# SHDN-IMD-S05-V00-IsolatedCAN.net
KiCad netlist of a schematic drawn in Altium Designer
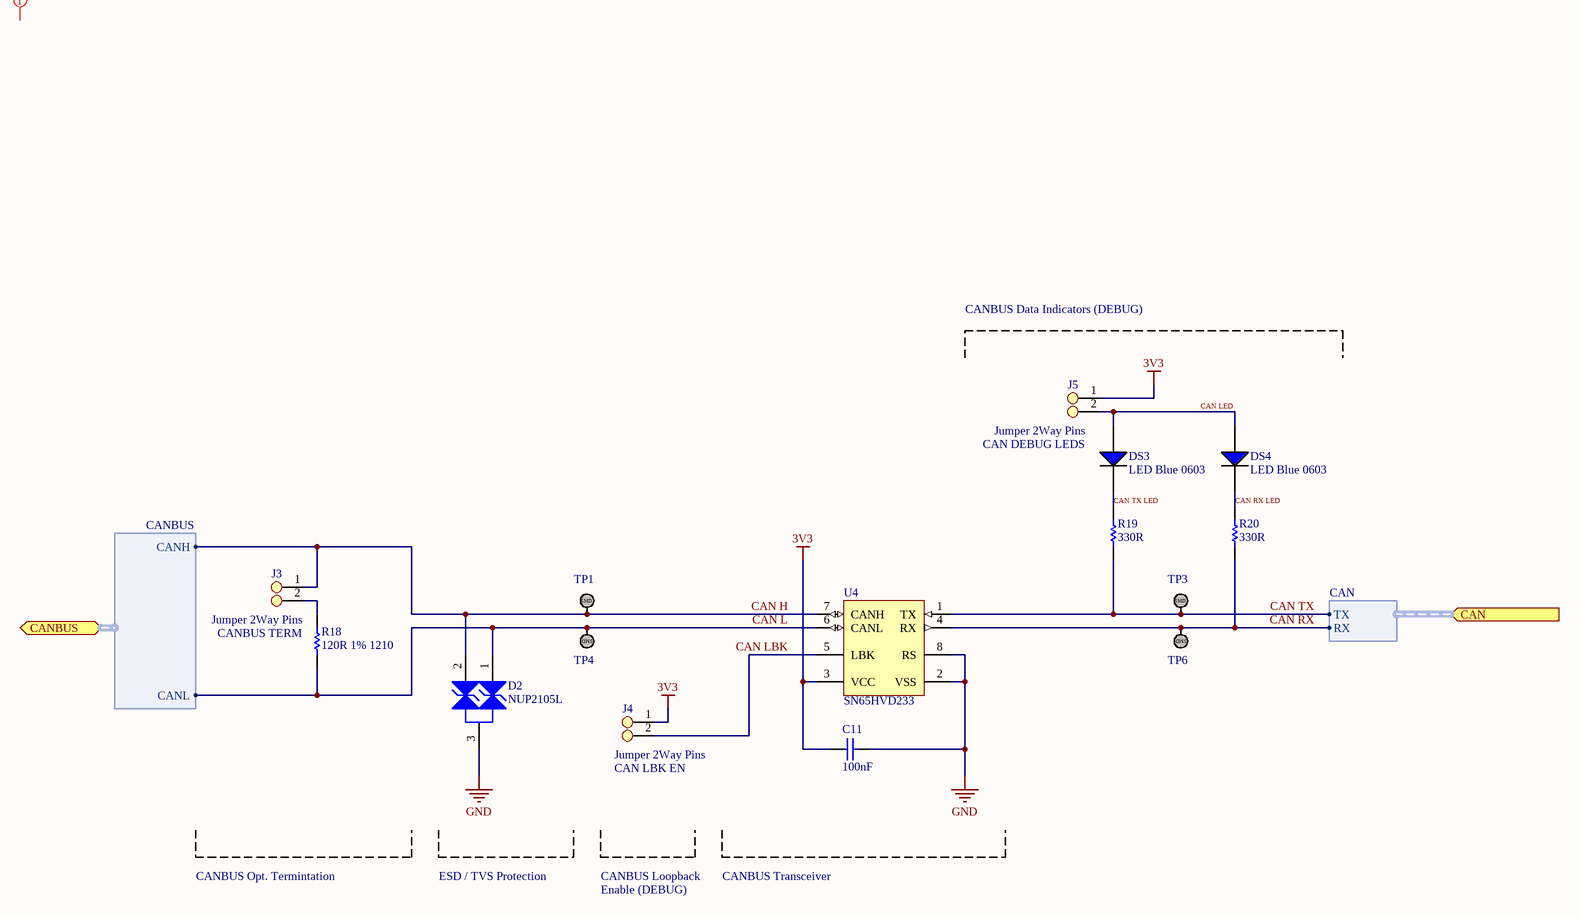
[diagram p0: SHDN-IMD-S05-V00-IsolatedCAN.SchDoc]

(export (version "E")
  (design (tool "Eeschema 10.0.6"))
  (components
    (comp (ref "C11")
      (value "100nF")
      (footprint "Cap_Ceramic_0603")
      (description "Capacitor, Ceramic, SMD, 100nF, 100V, 5%, X7R, 0603")
      (libsource (lib "StandardCapacitors") (part "100nF 100V 5% X7R 0603"))
    )
    (comp (ref "D2")
      (value "NUP2105L")
      (footprint "NUP2105L")
      (libsource (lib "QUTMS_CANLibrary") (part "NUP2105L"))
    )
    (comp (ref "DS3")
      (value "LED Blue 0603")
      (footprint "LED BLUE 0603")
      (libsource (lib "QUTMS_LEDLibrary") (part "LED BLUE 0603"))
    )
    (comp (ref "DS4")
      (value "LED Blue 0603")
      (footprint "LED BLUE 0603")
      (libsource (lib "QUTMS_LEDLibrary") (part "LED BLUE 0603"))
    )
    (comp (ref "J3")
      (value "Jumper 2Way Pins")
      (footprint "Jumper_2Way_Pin")
      (description "Jumper 2Way Side Pins")
      (libsource (lib "QUTMS_JumperLibrary") (part "Jumper 2Way Side Pins"))
    )
    (comp (ref "J4")
      (value "Jumper 2Way Pins")
      (footprint "Jumper_2Way_Pin")
      (description "Jumper 2Way Side Pins")
      (libsource (lib "QUTMS_JumperLibrary") (part "Jumper 2Way Side Pins"))
    )
    (comp (ref "J5")
      (value "Jumper 2Way Pins")
      (footprint "Jumper_2Way_Pin")
      (description "Jumper 2Way Side Pins")
      (libsource (lib "QUTMS_JumperLibrary") (part "Jumper 2Way Side Pins"))
    )
    (comp (ref "R18")
      (value "120R 1% 1210")
      (footprint "Res_ThinFilm_1210")
      (description "Resistor, SMD, 120R, 0.25W, 1%, 1210")
      (libsource (lib "StandardResistors") (part "120R 1% 1210"))
    )
    (comp (ref "R19")
      (value "330R")
      (footprint "Res_ThinFilm_0603")
      (description "Resistor, SMD, 330R, 0.1W, 5%, 0603")
      (libsource (lib "StandardResistors") (part "330R 5% 0603"))
    )
    (comp (ref "R20")
      (value "330R")
      (footprint "Res_ThinFilm_0603")
      (description "Resistor, SMD, 330R, 0.1W, 5%, 0603")
      (libsource (lib "StandardResistors") (part "330R 5% 0603"))
    )
    (comp (ref "TP1")
      (value "TestPoint_SMD")
      (footprint "TestPointSMD")
      (libsource (lib "StandardTest") (part "TestPoint_SMD"))
    )
    (comp (ref "TP3")
      (value "TestPoint_SMD")
      (footprint "TestPointSMD")
      (libsource (lib "StandardTest") (part "TestPoint_SMD"))
    )
    (comp (ref "TP4")
      (value "TestPoint_SMD")
      (footprint "TestPointSMD")
      (libsource (lib "StandardTest") (part "TestPoint_SMD"))
    )
    (comp (ref "TP6")
      (value "TestPoint_SMD")
      (footprint "TestPointSMD")
      (libsource (lib "StandardTest") (part "TestPoint_SMD"))
    )
    (comp (ref "U4")
      (value "SN65HVD233")
      (footprint "SN65HVD233DR")
      (libsource (lib "QUTMS_CANLibrary") (part "SN65HVD233"))
    )
  )
  (nets
    (net (code "3") (name "/CAN H") (class "Default")
      (node (ref "D2") (pin "2") (pinfunction "2_2") (pintype "passive"))
      (node (ref "J3") (pin "1") (pinfunction "1_1") (pintype "passive"))
      (node (ref "TP1") (pin "1") (pinfunction "1_1") (pintype "passive"))
      (node (ref "U4") (pin "7") (pinfunction "CANH_7") (pintype "bidirectional"))
    )
    (net (code "4") (name "/CAN L") (class "Default")
      (node (ref "D2") (pin "1") (pinfunction "1_1") (pintype "passive"))
      (node (ref "R18") (pin "1") (pinfunction "1_1") (pintype "passive"))
      (node (ref "TP4") (pin "1") (pinfunction "1_1") (pintype "passive"))
      (node (ref "U4") (pin "6") (pinfunction "CANL_6") (pintype "bidirectional"))
    )
    (net (code "5") (name "/CAN LBK") (class "Default")
      (node (ref "J4") (pin "2") (pinfunction "2_2") (pintype "passive"))
      (node (ref "U4") (pin "5") (pinfunction "LBK_5") (pintype "passive"))
    )
    (net (code "6") (name "/CAN LED") (class "Default")
      (node (ref "DS3") (pin "1") (pinfunction "A_1") (pintype "passive"))
      (node (ref "DS4") (pin "1") (pinfunction "A_1") (pintype "passive"))
      (node (ref "J5") (pin "2") (pinfunction "2_2") (pintype "passive"))
    )
    (net (code "7") (name "/CAN RX") (class "Default")
      (node (ref "R20") (pin "1") (pinfunction "1_1") (pintype "passive"))
      (node (ref "TP6") (pin "1") (pinfunction "1_1") (pintype "passive"))
      (node (ref "U4") (pin "4") (pinfunction "RX_4") (pintype "output"))
    )
    (net (code "8") (name "/CAN RX LED") (class "Default")
      (node (ref "DS4") (pin "2") (pinfunction "C_2") (pintype "passive"))
      (node (ref "R20") (pin "2") (pinfunction "2_2") (pintype "passive"))
    )
    (net (code "9") (name "/CAN TX") (class "Default")
      (node (ref "R19") (pin "1") (pinfunction "1_1") (pintype "passive"))
      (node (ref "TP3") (pin "1") (pinfunction "1_1") (pintype "passive"))
      (node (ref "U4") (pin "1") (pinfunction "TX_1") (pintype "input"))
    )
    (net (code "10") (name "/CAN TX LED") (class "Default")
      (node (ref "DS3") (pin "2") (pinfunction "C_2") (pintype "passive"))
      (node (ref "R19") (pin "2") (pinfunction "2_2") (pintype "passive"))
    )
    (net (code "13") (name "3V3") (class "Default")
      (node (ref "C11") (pin "1") (pinfunction "1_1") (pintype "passive"))
      (node (ref "J4") (pin "1") (pinfunction "1_1") (pintype "passive"))
      (node (ref "J5") (pin "1") (pinfunction "1_1") (pintype "passive"))
      (node (ref "U4") (pin "3") (pinfunction "VCC_3") (pintype "passive"))
    )
    (net (code "14") (name "GND") (class "Default")
      (node (ref "C11") (pin "2") (pinfunction "2_2") (pintype "passive"))
      (node (ref "D2") (pin "3") (pinfunction "3_3") (pintype "passive"))
      (node (ref "U4") (pin "2") (pinfunction "VSS_2") (pintype "passive"))
      (node (ref "U4") (pin "8") (pinfunction "RS_8") (pintype "passive"))
    )
    (net (code "15") (name "Net-(J3-Pad2)") (class "Default")
      (node (ref "J3") (pin "2") (pinfunction "2_2") (pintype "passive"))
      (node (ref "R18") (pin "2") (pinfunction "2_2") (pintype "passive"))
    )
  )
)
